# RPI_SmartServo_th.net
KiCad netlist of a schematic drawn in EAGLE
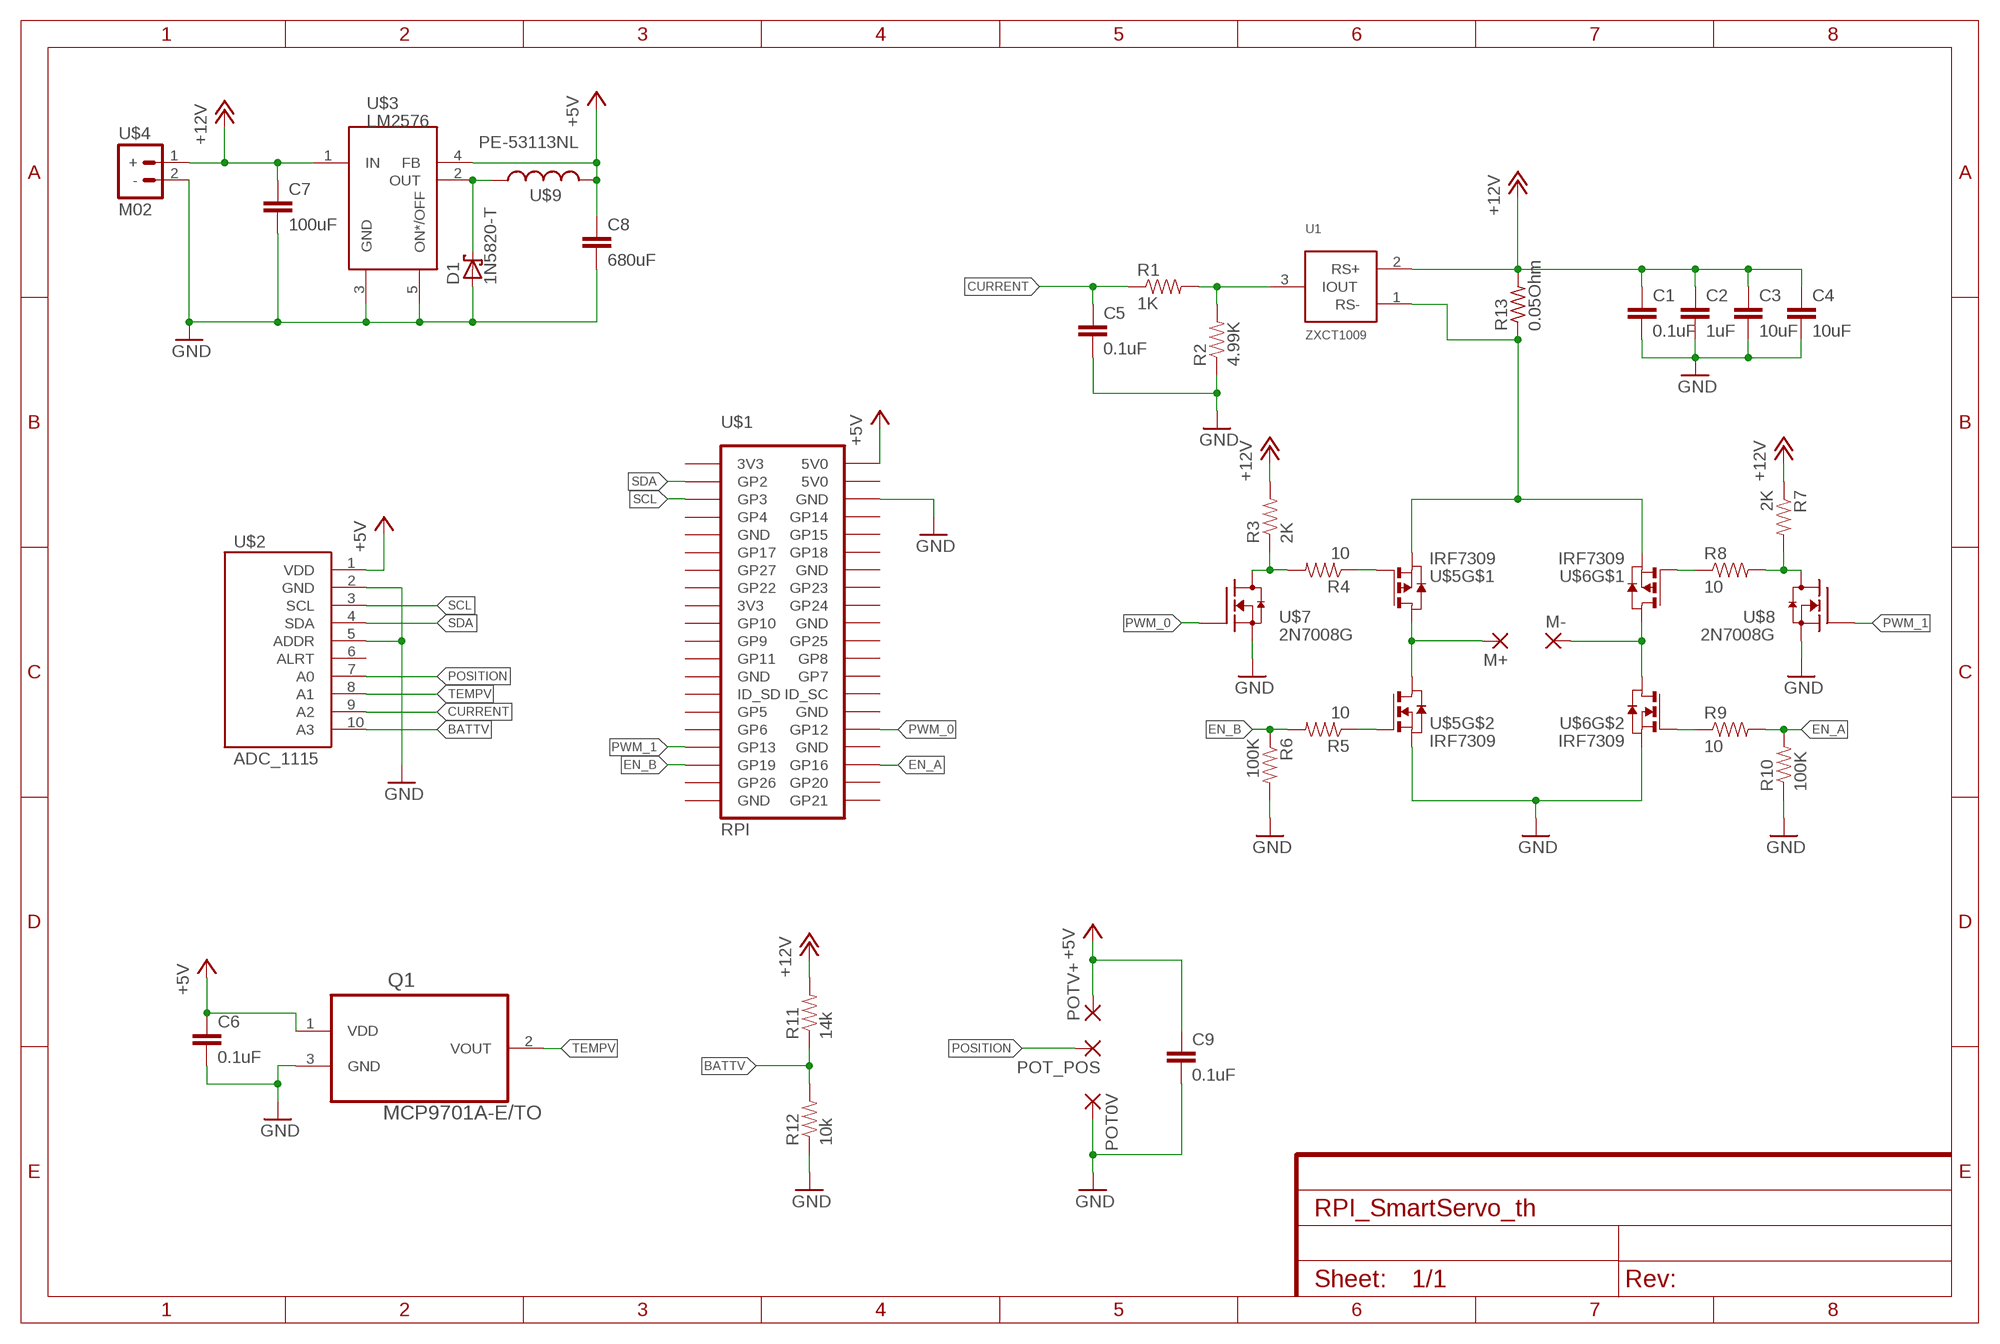
[diagram p0: schematic, sheet 1]

(export (version "E")
  (design (tool "Eeschema 10.0.6"))
  (components
    (comp (ref "C1")
      (value "0.1uF")
      (footprint "eagle-import:C025-025X050")
      (libsource (lib "eagle-import") (part "C-EU025-025X050"))
    )
    (comp (ref "C2")
      (value "1uF")
      (footprint "eagle-import:C025-025X050")
      (libsource (lib "eagle-import") (part "C-EU025-025X050"))
    )
    (comp (ref "C3")
      (value "10uF")
      (footprint "eagle-import:C025-025X050")
      (libsource (lib "eagle-import") (part "C-EU025-025X050"))
    )
    (comp (ref "C4")
      (value "10uF")
      (footprint "eagle-import:C025-025X050")
      (libsource (lib "eagle-import") (part "C-EU025-025X050"))
    )
    (comp (ref "C5")
      (value "0.1uF")
      (footprint "eagle-import:C025-025X050")
      (libsource (lib "eagle-import") (part "C-EU025-025X050"))
    )
    (comp (ref "C6")
      (value "0.1uF")
      (footprint "eagle-import:C025-025X050")
      (libsource (lib "eagle-import") (part "C-EU025-025X050"))
    )
    (comp (ref "C7")
      (value "100uF")
      (footprint "eagle-import:C025-025X050")
      (libsource (lib "eagle-import") (part "C-EU025-025X050"))
    )
    (comp (ref "C8")
      (value "680uF")
      (footprint "eagle-import:C025-025X050")
      (libsource (lib "eagle-import") (part "C-EU025-025X050"))
    )
    (comp (ref "C9")
      (value "0.1uF")
      (footprint "eagle-import:C025-025X050")
      (libsource (lib "eagle-import") (part "C-EU025-025X050"))
    )
    (comp (ref "D1")
      (value "1N5820-T")
      (footprint "eagle-import:C4111-15")
      (libsource (lib "eagle-import") (part "SCHOTTKY-DIODEC4111-15"))
    )
    (comp (ref "M+")
      (value "1,6/0,9")
      (footprint "eagle-import:1,6_0,9")
      (libsource (lib "eagle-import") (part "1,6/0,9"))
    )
    (comp (ref "M-")
      (value "1,6/0,9")
      (footprint "eagle-import:1,6_0,9")
      (libsource (lib "eagle-import") (part "1,6/0,9"))
    )
    (comp (ref "POT0V")
      (value "1,6/0,9")
      (footprint "eagle-import:1,6_0,9")
      (libsource (lib "eagle-import") (part "1,6/0,9"))
    )
    (comp (ref "POTV+")
      (value "1,6/0,9")
      (footprint "eagle-import:1,6_0,9")
      (libsource (lib "eagle-import") (part "1,6/0,9"))
    )
    (comp (ref "POT_POS")
      (value "1,6/0,9")
      (footprint "eagle-import:1,6_0,9")
      (libsource (lib "eagle-import") (part "1,6/0,9"))
    )
    (comp (ref "Q1")
      (value "MCP9701A-E/TO")
      (footprint "eagle-import:TO127P254X533-3")
      (libsource (lib "eagle-import") (part "MCP9701A-E/TO"))
    )
    (comp (ref "R1")
      (value "1K")
      (footprint "eagle-import:AXIAL-0.4")
      (libsource (lib "eagle-import") (part "RESISTORPTH-1/4W"))
    )
    (comp (ref "R2")
      (value "4.99K")
      (footprint "eagle-import:AXIAL-0.4")
      (libsource (lib "eagle-import") (part "RESISTORPTH-1/4W"))
    )
    (comp (ref "R3")
      (value "2K")
      (footprint "eagle-import:AXIAL-0.4")
      (libsource (lib "eagle-import") (part "RESISTORPTH-1/4W"))
    )
    (comp (ref "R4")
      (value "10")
      (footprint "eagle-import:AXIAL-0.4")
      (libsource (lib "eagle-import") (part "RESISTORPTH-1/4W"))
    )
    (comp (ref "R5")
      (value "10")
      (footprint "eagle-import:AXIAL-0.4")
      (libsource (lib "eagle-import") (part "RESISTORPTH-1/4W"))
    )
    (comp (ref "R6")
      (value "100K")
      (footprint "eagle-import:AXIAL-0.4")
      (libsource (lib "eagle-import") (part "RESISTORPTH-1/4W"))
    )
    (comp (ref "R7")
      (value "2K")
      (footprint "eagle-import:AXIAL-0.4")
      (libsource (lib "eagle-import") (part "RESISTORPTH-1/4W"))
    )
    (comp (ref "R8")
      (value "10")
      (footprint "eagle-import:AXIAL-0.4")
      (libsource (lib "eagle-import") (part "RESISTORPTH-1/4W"))
    )
    (comp (ref "R9")
      (value "10")
      (footprint "eagle-import:AXIAL-0.4")
      (libsource (lib "eagle-import") (part "RESISTORPTH-1/4W"))
    )
    (comp (ref "R10")
      (value "100K")
      (footprint "eagle-import:AXIAL-0.4")
      (libsource (lib "eagle-import") (part "RESISTORPTH-1/4W"))
    )
    (comp (ref "R11")
      (value "14k")
      (footprint "eagle-import:AXIAL-0.4")
      (libsource (lib "eagle-import") (part "RESISTORPTH-1/4W"))
    )
    (comp (ref "R12")
      (value "10k")
      (footprint "eagle-import:AXIAL-0.4")
      (libsource (lib "eagle-import") (part "RESISTORPTH-1/4W"))
    )
    (comp (ref "R13")
      (value "0.05Ohm")
      (footprint "eagle-import:0922_22")
      (libsource (lib "eagle-import") (part "R-US_0922/22"))
    )
    (comp (ref "U$1")
      (value "RPI")
      (footprint "eagle-import:2X20")
      (libsource (lib "eagle-import") (part "RPI"))
    )
    (comp (ref "U$2")
      (value "ADC_1115")
      (footprint "eagle-import:1X10")
      (libsource (lib "eagle-import") (part "ADC_1115"))
    )
    (comp (ref "U$3")
      (value "LM2576")
      (footprint "eagle-import:LM2576")
      (libsource (lib "eagle-import") (part "LM2576"))
    )
    (comp (ref "U$4")
      (value "M02")
      (footprint "eagle-import:1X02")
      (libsource (lib "eagle-import") (part "M02"))
    )
    (comp (ref "U$5")
      (value "IRF7309")
      (footprint "eagle-import:SO8")
      (libsource (lib "eagle-import") (part "IRF7309"))
    )
    (comp (ref "U$6")
      (value "IRF7309")
      (footprint "eagle-import:SO8")
      (libsource (lib "eagle-import") (part "IRF7309"))
    )
    (comp (ref "U$7")
      (value "2N7008G")
      (footprint "eagle-import:TO-92")
      (libsource (lib "eagle-import") (part "2N7008G"))
    )
    (comp (ref "U$8")
      (value "2N7008G")
      (footprint "eagle-import:TO-92")
      (libsource (lib "eagle-import") (part "2N7008G"))
    )
    (comp (ref "U$9")
      (value "PE-53113NL")
      (footprint "eagle-import:KM-4")
      (libsource (lib "eagle-import") (part "PE-53113NL"))
    )
    (comp (ref "U1")
      (value "ZXCT1009")
      (footprint "eagle-import:SOT23")
      (libsource (lib "eagle-import") (part "ZXCT1009"))
    )
  )
  (nets
    (net (code "1") (name "+5V") (class "Default")
      (node (ref "C6") (pin "1") (pinfunction "1_1") (pintype "passive"))
      (node (ref "C8") (pin "1") (pinfunction "1_1") (pintype "passive"))
      (node (ref "C9") (pin "1") (pinfunction "1_1") (pintype "passive"))
      (node (ref "POTV+") (pin "1") (pinfunction "P_1") (pintype "passive"))
      (node (ref "Q1") (pin "1") (pinfunction "VDD_1") (pintype "power_in"))
      (node (ref "U$1") (pin "2") (pinfunction "5V0_2") (pintype "bidirectional"))
      (node (ref "U$2") (pin "1") (pinfunction "VDD_1") (pintype "bidirectional"))
      (node (ref "U$3") (pin "4") (pinfunction "FB_4") (pintype "bidirectional"))
      (node (ref "U$9") (pin "P$2") (pinfunction "2_P$2") (pintype "passive"))
    )
    (net (code "2") (name "+12V") (class "Default")
      (node (ref "C1") (pin "1") (pinfunction "1_1") (pintype "passive"))
      (node (ref "C2") (pin "1") (pinfunction "1_1") (pintype "passive"))
      (node (ref "C3") (pin "1") (pinfunction "1_1") (pintype "passive"))
      (node (ref "C4") (pin "1") (pinfunction "1_1") (pintype "passive"))
      (node (ref "C7") (pin "1") (pinfunction "1_1") (pintype "passive"))
      (node (ref "R11") (pin "P$2") (pinfunction "2_P$2") (pintype "passive"))
      (node (ref "R13") (pin "2") (pinfunction "2_2") (pintype "passive"))
      (node (ref "R3") (pin "P$2") (pinfunction "2_P$2") (pintype "passive"))
      (node (ref "R7") (pin "P$1") (pinfunction "1_P$1") (pintype "passive"))
      (node (ref "U$3") (pin "1") (pinfunction "IN_1") (pintype "bidirectional"))
      (node (ref "U$4") (pin "1") (pinfunction "+_1") (pintype "passive"))
      (node (ref "U1") (pin "2") (pinfunction "RS+_2") (pintype "bidirectional"))
    )
    (net (code "3") (name "BATTV") (class "Default")
      (node (ref "R11") (pin "P$1") (pinfunction "1_P$1") (pintype "passive"))
      (node (ref "R12") (pin "P$2") (pinfunction "2_P$2") (pintype "passive"))
      (node (ref "U$2") (pin "10") (pinfunction "A3_10") (pintype "bidirectional"))
    )
    (net (code "4") (name "CURRENT") (class "Default")
      (node (ref "C5") (pin "1") (pinfunction "1_1") (pintype "passive"))
      (node (ref "R1") (pin "P$1") (pinfunction "1_P$1") (pintype "passive"))
      (node (ref "U$2") (pin "9") (pinfunction "A2_9") (pintype "bidirectional"))
    )
    (net (code "5") (name "EN_A") (class "Default")
      (node (ref "R10") (pin "P$2") (pinfunction "2_P$2") (pintype "passive"))
      (node (ref "R9") (pin "P$2") (pinfunction "2_P$2") (pintype "passive"))
      (node (ref "U$1") (pin "36") (pinfunction "GP16_36") (pintype "bidirectional"))
    )
    (net (code "6") (name "EN_B") (class "Default")
      (node (ref "R5") (pin "P$2") (pinfunction "2_P$2") (pintype "passive"))
      (node (ref "R6") (pin "P$1") (pinfunction "1_P$1") (pintype "passive"))
      (node (ref "U$1") (pin "35") (pinfunction "GP19_35") (pintype "bidirectional"))
    )
    (net (code "7") (name "GND") (class "Default")
      (node (ref "C1") (pin "2") (pinfunction "2_2") (pintype "passive"))
      (node (ref "C2") (pin "2") (pinfunction "2_2") (pintype "passive"))
      (node (ref "C3") (pin "2") (pinfunction "2_2") (pintype "passive"))
      (node (ref "C4") (pin "2") (pinfunction "2_2") (pintype "passive"))
      (node (ref "C5") (pin "2") (pinfunction "2_2") (pintype "passive"))
      (node (ref "C6") (pin "2") (pinfunction "2_2") (pintype "passive"))
      (node (ref "C7") (pin "2") (pinfunction "2_2") (pintype "passive"))
      (node (ref "C8") (pin "2") (pinfunction "2_2") (pintype "passive"))
      (node (ref "C9") (pin "2") (pinfunction "2_2") (pintype "passive"))
      (node (ref "D1") (pin "A") (pinfunction "A_A") (pintype "passive"))
      (node (ref "POT0V") (pin "1") (pinfunction "P_1") (pintype "passive"))
      (node (ref "Q1") (pin "3") (pinfunction "GND_3") (pintype "passive"))
      (node (ref "R10") (pin "P$1") (pinfunction "1_P$1") (pintype "passive"))
      (node (ref "R12") (pin "P$1") (pinfunction "1_P$1") (pintype "passive"))
      (node (ref "R2") (pin "P$1") (pinfunction "1_P$1") (pintype "passive"))
      (node (ref "R6") (pin "P$2") (pinfunction "2_P$2") (pintype "passive"))
      (node (ref "U$1") (pin "6") (pinfunction "GND_6") (pintype "bidirectional"))
      (node (ref "U$2") (pin "2") (pinfunction "GND_2") (pintype "bidirectional"))
      (node (ref "U$2") (pin "5") (pinfunction "ADDR_5") (pintype "bidirectional"))
      (node (ref "U$3") (pin "3") (pinfunction "GND_3") (pintype "bidirectional"))
      (node (ref "U$3") (pin "5") (pinfunction "ON*/OFF_5") (pintype "bidirectional"))
      (node (ref "U$4") (pin "2") (pinfunction "-_2") (pintype "passive"))
      (node (ref "U$5") (pin "1") (pinfunction "S_1") (pintype "passive"))
      (node (ref "U$6") (pin "1") (pinfunction "S_1") (pintype "passive"))
      (node (ref "U$7") (pin "1") (pinfunction "S_1") (pintype "passive"))
      (node (ref "U$8") (pin "1") (pinfunction "S_1") (pintype "passive"))
    )
    (net (code "8") (name "Net-(M+-P)") (class "Default")
      (node (ref "M+") (pin "1") (pinfunction "P_1") (pintype "passive"))
      (node (ref "U$5") (pin "5") (pinfunction "D_5") (pintype "passive"))
      (node (ref "U$5") (pin "6") (pinfunction "D_6") (pintype "passive"))
      (node (ref "U$5") (pin "7") (pinfunction "D_7") (pintype "passive"))
      (node (ref "U$5") (pin "8") (pinfunction "D_8") (pintype "passive"))
    )
    (net (code "9") (name "Net-(M--P)") (class "Default")
      (node (ref "M-") (pin "1") (pinfunction "P_1") (pintype "passive"))
      (node (ref "U$6") (pin "5") (pinfunction "D_5") (pintype "passive"))
      (node (ref "U$6") (pin "6") (pinfunction "D_6") (pintype "passive"))
      (node (ref "U$6") (pin "7") (pinfunction "D_7") (pintype "passive"))
      (node (ref "U$6") (pin "8") (pinfunction "D_8") (pintype "passive"))
    )
    (net (code "10") (name "Net-(R1-2)") (class "Default")
      (node (ref "R1") (pin "P$2") (pinfunction "2_P$2") (pintype "passive"))
      (node (ref "R2") (pin "P$2") (pinfunction "2_P$2") (pintype "passive"))
      (node (ref "U1") (pin "3") (pinfunction "IOUT_3") (pintype "bidirectional"))
    )
    (net (code "11") (name "Net-(R3-1)") (class "Default")
      (node (ref "R3") (pin "P$1") (pinfunction "1_P$1") (pintype "passive"))
      (node (ref "R4") (pin "P$2") (pinfunction "2_P$2") (pintype "passive"))
      (node (ref "U$7") (pin "3") (pinfunction "D_3") (pintype "passive"))
    )
    (net (code "12") (name "Net-(R4-1)") (class "Default")
      (node (ref "R4") (pin "P$1") (pinfunction "1_P$1") (pintype "passive"))
      (node (ref "U$5") (pin "4") (pinfunction "G_4") (pintype "passive"))
    )
    (net (code "13") (name "Net-(R5-1)") (class "Default")
      (node (ref "R5") (pin "P$1") (pinfunction "1_P$1") (pintype "passive"))
      (node (ref "U$5") (pin "2") (pinfunction "G_2") (pintype "passive"))
    )
    (net (code "14") (name "Net-(R7-2)") (class "Default")
      (node (ref "R7") (pin "P$2") (pinfunction "2_P$2") (pintype "passive"))
      (node (ref "R8") (pin "P$2") (pinfunction "2_P$2") (pintype "passive"))
      (node (ref "U$8") (pin "3") (pinfunction "D_3") (pintype "passive"))
    )
    (net (code "15") (name "Net-(R8-1)") (class "Default")
      (node (ref "R8") (pin "P$1") (pinfunction "1_P$1") (pintype "passive"))
      (node (ref "U$6") (pin "4") (pinfunction "G_4") (pintype "passive"))
    )
    (net (code "16") (name "Net-(R9-1)") (class "Default")
      (node (ref "R9") (pin "P$1") (pinfunction "1_P$1") (pintype "passive"))
      (node (ref "U$6") (pin "2") (pinfunction "G_2") (pintype "passive"))
    )
    (net (code "17") (name "Net-(U$3-OUT)") (class "Default")
      (node (ref "D1") (pin "C") (pinfunction "C_C") (pintype "passive"))
      (node (ref "U$3") (pin "2") (pinfunction "OUT_2") (pintype "bidirectional"))
      (node (ref "U$9") (pin "P$1") (pinfunction "1_P$1") (pintype "passive"))
    )
    (net (code "18") (name "Net-(U$5A-S)") (class "Default")
      (node (ref "R13") (pin "1") (pinfunction "1_1") (pintype "passive"))
      (node (ref "U$5") (pin "3") (pinfunction "S_3") (pintype "passive"))
      (node (ref "U$6") (pin "3") (pinfunction "S_3") (pintype "passive"))
      (node (ref "U1") (pin "1") (pinfunction "RS-_1") (pintype "bidirectional"))
    )
    (net (code "19") (name "POSITION") (class "Default")
      (node (ref "POT_POS") (pin "1") (pinfunction "P_1") (pintype "passive"))
      (node (ref "U$2") (pin "7") (pinfunction "A0_7") (pintype "bidirectional"))
    )
    (net (code "20") (name "PWM_0") (class "Default")
      (node (ref "U$1") (pin "32") (pinfunction "GP12_32") (pintype "bidirectional"))
      (node (ref "U$7") (pin "2") (pinfunction "G_2") (pintype "passive"))
    )
    (net (code "21") (name "PWM_1") (class "Default")
      (node (ref "U$1") (pin "33") (pinfunction "GP13_33") (pintype "bidirectional"))
      (node (ref "U$8") (pin "2") (pinfunction "G_2") (pintype "passive"))
    )
    (net (code "22") (name "SCL") (class "Default")
      (node (ref "U$1") (pin "5") (pinfunction "GP3_5") (pintype "bidirectional"))
      (node (ref "U$2") (pin "3") (pinfunction "SCL_3") (pintype "bidirectional"))
    )
    (net (code "23") (name "SDA") (class "Default")
      (node (ref "U$1") (pin "3") (pinfunction "GP2_3") (pintype "bidirectional"))
      (node (ref "U$2") (pin "4") (pinfunction "SDA_4") (pintype "bidirectional"))
    )
    (net (code "24") (name "TEMPV") (class "Default")
      (node (ref "Q1") (pin "2") (pinfunction "VOUT_2") (pintype "output"))
      (node (ref "U$2") (pin "8") (pinfunction "A1_8") (pintype "bidirectional"))
    )
    (net (code "25") (name "unconnected-(U$1-3V3-Pad1)") (class "Default")
      (node (ref "U$1") (pin "1") (pinfunction "3V3_1") (pintype "bidirectional"))
    )
    (net (code "26") (name "unconnected-(U$1-3V3-Pad17)") (class "Default")
      (node (ref "U$1") (pin "17") (pinfunction "3V3_17") (pintype "bidirectional"))
    )
    (net (code "27") (name "unconnected-(U$1-5V0-Pad4)") (class "Default")
      (node (ref "U$1") (pin "4") (pinfunction "5V0_4") (pintype "bidirectional"))
    )
    (net (code "28") (name "unconnected-(U$1-GND-Pad9)") (class "Default")
      (node (ref "U$1") (pin "9") (pinfunction "GND_9") (pintype "bidirectional"))
    )
    (net (code "29") (name "unconnected-(U$1-GND-Pad14)") (class "Default")
      (node (ref "U$1") (pin "14") (pinfunction "GND_14") (pintype "bidirectional"))
    )
    (net (code "30") (name "unconnected-(U$1-GND-Pad20)") (class "Default")
      (node (ref "U$1") (pin "20") (pinfunction "GND_20") (pintype "bidirectional"))
    )
    (net (code "31") (name "unconnected-(U$1-GND-Pad25)") (class "Default")
      (node (ref "U$1") (pin "25") (pinfunction "GND_25") (pintype "bidirectional"))
    )
    (net (code "32") (name "unconnected-(U$1-GND-Pad30)") (class "Default")
      (node (ref "U$1") (pin "30") (pinfunction "GND_30") (pintype "bidirectional"))
    )
    (net (code "33") (name "unconnected-(U$1-GND-Pad34)") (class "Default")
      (node (ref "U$1") (pin "34") (pinfunction "GND_34") (pintype "bidirectional"))
    )
    (net (code "34") (name "unconnected-(U$1-GND-Pad39)") (class "Default")
      (node (ref "U$1") (pin "39") (pinfunction "GND_39") (pintype "bidirectional"))
    )
    (net (code "35") (name "unconnected-(U$1-GP4-Pad7)") (class "Default")
      (node (ref "U$1") (pin "7") (pinfunction "GP4_7") (pintype "bidirectional"))
    )
    (net (code "36") (name "unconnected-(U$1-GP5-Pad29)") (class "Default")
      (node (ref "U$1") (pin "29") (pinfunction "GP5_29") (pintype "bidirectional"))
    )
    (net (code "37") (name "unconnected-(U$1-GP6-Pad31)") (class "Default")
      (node (ref "U$1") (pin "31") (pinfunction "GP6_31") (pintype "bidirectional"))
    )
    (net (code "38") (name "unconnected-(U$1-GP7-Pad26)") (class "Default")
      (node (ref "U$1") (pin "26") (pinfunction "GP7_26") (pintype "bidirectional"))
    )
    (net (code "39") (name "unconnected-(U$1-GP8-Pad24)") (class "Default")
      (node (ref "U$1") (pin "24") (pinfunction "GP8_24") (pintype "bidirectional"))
    )
    (net (code "40") (name "unconnected-(U$1-GP9-Pad21)") (class "Default")
      (node (ref "U$1") (pin "21") (pinfunction "GP9_21") (pintype "bidirectional"))
    )
    (net (code "41") (name "unconnected-(U$1-GP10-Pad19)") (class "Default")
      (node (ref "U$1") (pin "19") (pinfunction "GP10_19") (pintype "bidirectional"))
    )
    (net (code "42") (name "unconnected-(U$1-GP11-Pad23)") (class "Default")
      (node (ref "U$1") (pin "23") (pinfunction "GP11_23") (pintype "bidirectional"))
    )
    (net (code "43") (name "unconnected-(U$1-GP14-Pad8)") (class "Default")
      (node (ref "U$1") (pin "8") (pinfunction "GP14_8") (pintype "bidirectional"))
    )
    (net (code "44") (name "unconnected-(U$1-GP15-Pad10)") (class "Default")
      (node (ref "U$1") (pin "10") (pinfunction "GP15_10") (pintype "bidirectional"))
    )
    (net (code "45") (name "unconnected-(U$1-GP17-Pad11)") (class "Default")
      (node (ref "U$1") (pin "11") (pinfunction "GP17_11") (pintype "bidirectional"))
    )
    (net (code "46") (name "unconnected-(U$1-GP18-Pad12)") (class "Default")
      (node (ref "U$1") (pin "12") (pinfunction "GP18_12") (pintype "bidirectional"))
    )
    (net (code "47") (name "unconnected-(U$1-GP20-Pad38)") (class "Default")
      (node (ref "U$1") (pin "38") (pinfunction "GP20_38") (pintype "bidirectional"))
    )
    (net (code "48") (name "unconnected-(U$1-GP21-Pad40)") (class "Default")
      (node (ref "U$1") (pin "40") (pinfunction "GP21_40") (pintype "bidirectional"))
    )
    (net (code "49") (name "unconnected-(U$1-GP22-Pad15)") (class "Default")
      (node (ref "U$1") (pin "15") (pinfunction "GP22_15") (pintype "bidirectional"))
    )
    (net (code "50") (name "unconnected-(U$1-GP23-Pad16)") (class "Default")
      (node (ref "U$1") (pin "16") (pinfunction "GP23_16") (pintype "bidirectional"))
    )
    (net (code "51") (name "unconnected-(U$1-GP24-Pad18)") (class "Default")
      (node (ref "U$1") (pin "18") (pinfunction "GP24_18") (pintype "bidirectional"))
    )
    (net (code "52") (name "unconnected-(U$1-GP25-Pad22)") (class "Default")
      (node (ref "U$1") (pin "22") (pinfunction "GP25_22") (pintype "bidirectional"))
    )
    (net (code "53") (name "unconnected-(U$1-GP26-Pad37)") (class "Default")
      (node (ref "U$1") (pin "37") (pinfunction "GP26_37") (pintype "bidirectional"))
    )
    (net (code "54") (name "unconnected-(U$1-GP27-Pad13)") (class "Default")
      (node (ref "U$1") (pin "13") (pinfunction "GP27_13") (pintype "bidirectional"))
    )
    (net (code "55") (name "unconnected-(U$1-ID_SC-Pad28)") (class "Default")
      (node (ref "U$1") (pin "28") (pinfunction "ID_SC_28") (pintype "bidirectional"))
    )
    (net (code "56") (name "unconnected-(U$1-ID_SD-Pad27)") (class "Default")
      (node (ref "U$1") (pin "27") (pinfunction "ID_SD_27") (pintype "bidirectional"))
    )
    (net (code "57") (name "unconnected-(U$2-ALRT-Pad6)") (class "Default")
      (node (ref "U$2") (pin "6") (pinfunction "ALRT_6") (pintype "bidirectional"))
    )
  )
)
